# M783.net
KiCad netlist of a schematic drawn in EAGLE
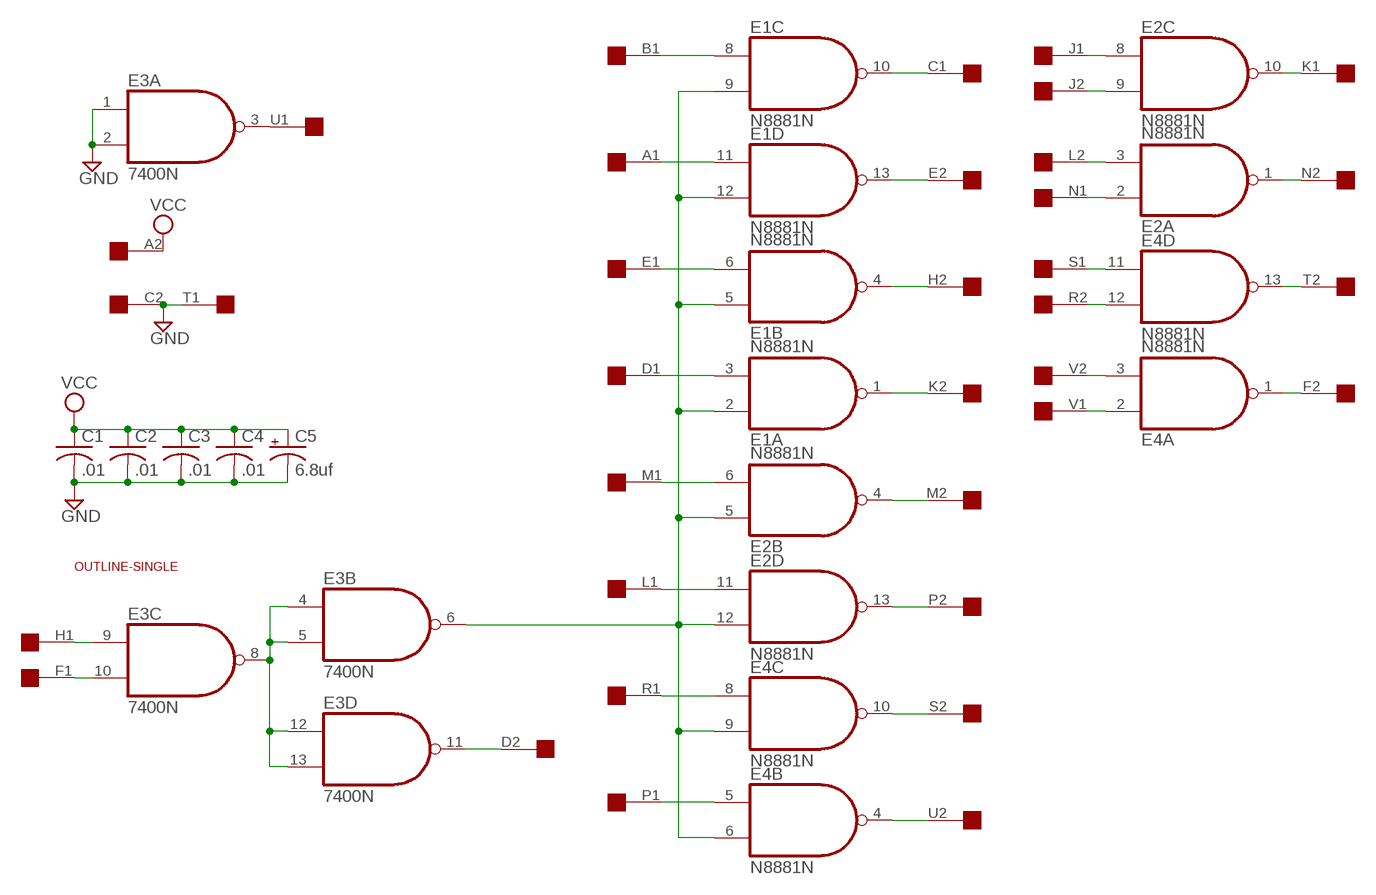
[diagram p0: schematic, sheet 1]

(export (version "E")
  (design (tool "Eeschema 10.0.6"))
  (components
    (comp (ref "C1")
      (value ".01")
      (footprint "eagle-import:C050-025X075")
      (libsource (lib "eagle-import") (part "C-US050-025X075"))
    )
    (comp (ref "C2")
      (value ".01")
      (footprint "eagle-import:C050-025X075")
      (libsource (lib "eagle-import") (part "C-US050-025X075"))
    )
    (comp (ref "C3")
      (value ".01")
      (footprint "eagle-import:C050-025X075")
      (libsource (lib "eagle-import") (part "C-US050-025X075"))
    )
    (comp (ref "C4")
      (value ".01")
      (footprint "eagle-import:C050-025X075")
      (libsource (lib "eagle-import") (part "C-US050-025X075"))
    )
    (comp (ref "C5")
      (value "6.8uf")
      (footprint "eagle-import:E15-5")
      (libsource (lib "eagle-import") (part "CPOL-USE15-5AXIAL"))
    )
    (comp (ref "E1")
      (value "N8881N")
      (footprint "eagle-import:DIL14")
      (libsource (lib "eagle-import") (part "N8881N"))
    )
    (comp (ref "E2")
      (value "N8881N")
      (footprint "eagle-import:DIL14")
      (libsource (lib "eagle-import") (part "N8881N"))
    )
    (comp (ref "E3")
      (value "7400N")
      (footprint "eagle-import:DIL14")
      (libsource (lib "eagle-import") (part "7400N"))
    )
    (comp (ref "E4")
      (value "N8881N")
      (footprint "eagle-import:DIL14")
      (libsource (lib "eagle-import") (part "N8881N"))
    )
    (comp (ref "U$1")
      (value "SINGLE")
      (footprint "eagle-import:EDGE-CON2")
      (libsource (lib "eagle-import") (part "SINGLE"))
    )
    (comp (ref "U$2")
      (value "OUTLINE-SINGLE")
      (footprint "eagle-import:SINGLE")
      (libsource (lib "eagle-import") (part "OUTLINE-SINGLE"))
    )
  )
  (nets
    (net (code "1") (name "GND") (class "Default")
      (node (ref "C1") (pin "2") (pinfunction "2_2") (pintype "passive"))
      (node (ref "C2") (pin "2") (pinfunction "2_2") (pintype "passive"))
      (node (ref "C3") (pin "2") (pinfunction "2_2") (pintype "passive"))
      (node (ref "C4") (pin "2") (pinfunction "2_2") (pintype "passive"))
      (node (ref "C5") (pin "-") (pinfunction "-_-") (pintype "passive"))
      (node (ref "E3") (pin "1") (pinfunction "I0_1") (pintype "input"))
      (node (ref "E3") (pin "2") (pinfunction "I1_2") (pintype "input"))
      (node (ref "U$1") (pin "C2") (pinfunction "1_C2") (pintype "bidirectional"))
      (node (ref "U$1") (pin "T1") (pinfunction "1_T1") (pintype "bidirectional"))
    )
    (net (code "2") (name "Net-(E1A-I0)") (class "Default")
      (node (ref "E1") (pin "12") (pinfunction "I1_12") (pintype "input"))
      (node (ref "E1") (pin "2") (pinfunction "I0_2") (pintype "input"))
      (node (ref "E1") (pin "5") (pinfunction "I0_5") (pintype "input"))
      (node (ref "E1") (pin "9") (pinfunction "I1_9") (pintype "input"))
      (node (ref "E2") (pin "12") (pinfunction "I1_12") (pintype "input"))
      (node (ref "E2") (pin "5") (pinfunction "I0_5") (pintype "input"))
      (node (ref "E3") (pin "6") (pinfunction "O_6") (pintype "output"))
      (node (ref "E4") (pin "6") (pinfunction "I1_6") (pintype "input"))
      (node (ref "E4") (pin "9") (pinfunction "I1_9") (pintype "input"))
    )
    (net (code "3") (name "Net-(E1A-I1)") (class "Default")
      (node (ref "E1") (pin "3") (pinfunction "I1_3") (pintype "input"))
      (node (ref "U$1") (pin "D1") (pinfunction "1_D1") (pintype "bidirectional"))
    )
    (net (code "4") (name "Net-(E1A-O)") (class "Default")
      (node (ref "E1") (pin "1") (pinfunction "O_1") (pintype "open_collector"))
      (node (ref "U$1") (pin "K2") (pinfunction "1_K2") (pintype "bidirectional"))
    )
    (net (code "5") (name "Net-(E1B-I1)") (class "Default")
      (node (ref "E1") (pin "6") (pinfunction "I1_6") (pintype "input"))
      (node (ref "U$1") (pin "E1") (pinfunction "1_E1") (pintype "bidirectional"))
    )
    (net (code "6") (name "Net-(E1B-O)") (class "Default")
      (node (ref "E1") (pin "4") (pinfunction "O_4") (pintype "open_collector"))
      (node (ref "U$1") (pin "H2") (pinfunction "1_H2") (pintype "bidirectional"))
    )
    (net (code "7") (name "Net-(E1C-I0)") (class "Default")
      (node (ref "E1") (pin "8") (pinfunction "I0_8") (pintype "input"))
      (node (ref "U$1") (pin "B1") (pinfunction "1_B1") (pintype "bidirectional"))
    )
    (net (code "8") (name "Net-(E1C-O)") (class "Default")
      (node (ref "E1") (pin "10") (pinfunction "O_10") (pintype "open_collector"))
      (node (ref "U$1") (pin "C1") (pinfunction "1_C1") (pintype "bidirectional"))
    )
    (net (code "9") (name "Net-(E1D-I0)") (class "Default")
      (node (ref "E1") (pin "11") (pinfunction "I0_11") (pintype "input"))
      (node (ref "U$1") (pin "A1") (pinfunction "1_A1") (pintype "bidirectional"))
    )
    (net (code "10") (name "Net-(E1D-O)") (class "Default")
      (node (ref "E1") (pin "13") (pinfunction "O_13") (pintype "open_collector"))
      (node (ref "U$1") (pin "E2") (pinfunction "1_E2") (pintype "bidirectional"))
    )
    (net (code "11") (name "Net-(E2A-I0)") (class "Default")
      (node (ref "E2") (pin "2") (pinfunction "I0_2") (pintype "input"))
      (node (ref "U$1") (pin "N1") (pinfunction "1_N1") (pintype "bidirectional"))
    )
    (net (code "12") (name "Net-(E2A-I1)") (class "Default")
      (node (ref "E2") (pin "3") (pinfunction "I1_3") (pintype "input"))
      (node (ref "U$1") (pin "L2") (pinfunction "1_L2") (pintype "bidirectional"))
    )
    (net (code "13") (name "Net-(E2A-O)") (class "Default")
      (node (ref "E2") (pin "1") (pinfunction "O_1") (pintype "open_collector"))
      (node (ref "U$1") (pin "N2") (pinfunction "1_N2") (pintype "bidirectional"))
    )
    (net (code "14") (name "Net-(E2B-I1)") (class "Default")
      (node (ref "E2") (pin "6") (pinfunction "I1_6") (pintype "input"))
      (node (ref "U$1") (pin "M1") (pinfunction "1_M1") (pintype "bidirectional"))
    )
    (net (code "15") (name "Net-(E2B-O)") (class "Default")
      (node (ref "E2") (pin "4") (pinfunction "O_4") (pintype "open_collector"))
      (node (ref "U$1") (pin "M2") (pinfunction "1_M2") (pintype "bidirectional"))
    )
    (net (code "16") (name "Net-(E2C-I0)") (class "Default")
      (node (ref "E2") (pin "8") (pinfunction "I0_8") (pintype "input"))
      (node (ref "U$1") (pin "J1") (pinfunction "1_J1") (pintype "bidirectional"))
    )
    (net (code "17") (name "Net-(E2C-I1)") (class "Default")
      (node (ref "E2") (pin "9") (pinfunction "I1_9") (pintype "input"))
      (node (ref "U$1") (pin "J2") (pinfunction "1_J2") (pintype "bidirectional"))
    )
    (net (code "18") (name "Net-(E2C-O)") (class "Default")
      (node (ref "E2") (pin "10") (pinfunction "O_10") (pintype "open_collector"))
      (node (ref "U$1") (pin "K1") (pinfunction "1_K1") (pintype "bidirectional"))
    )
    (net (code "19") (name "Net-(E2D-I0)") (class "Default")
      (node (ref "E2") (pin "11") (pinfunction "I0_11") (pintype "input"))
      (node (ref "U$1") (pin "L1") (pinfunction "1_L1") (pintype "bidirectional"))
    )
    (net (code "20") (name "Net-(E2D-O)") (class "Default")
      (node (ref "E2") (pin "13") (pinfunction "O_13") (pintype "open_collector"))
      (node (ref "U$1") (pin "P2") (pinfunction "1_P2") (pintype "bidirectional"))
    )
    (net (code "21") (name "Net-(E3A-O)") (class "Default")
      (node (ref "E3") (pin "3") (pinfunction "O_3") (pintype "output"))
      (node (ref "U$1") (pin "U1") (pinfunction "1_U1") (pintype "bidirectional"))
    )
    (net (code "22") (name "Net-(E3B-I0)") (class "Default")
      (node (ref "E3") (pin "12") (pinfunction "I0_12") (pintype "input"))
      (node (ref "E3") (pin "13") (pinfunction "I1_13") (pintype "input"))
      (node (ref "E3") (pin "4") (pinfunction "I0_4") (pintype "input"))
      (node (ref "E3") (pin "5") (pinfunction "I1_5") (pintype "input"))
      (node (ref "E3") (pin "8") (pinfunction "O_8") (pintype "output"))
    )
    (net (code "23") (name "Net-(E3C-I0)") (class "Default")
      (node (ref "E3") (pin "9") (pinfunction "I0_9") (pintype "input"))
      (node (ref "U$1") (pin "H1") (pinfunction "1_H1") (pintype "bidirectional"))
    )
    (net (code "24") (name "Net-(E3C-I1)") (class "Default")
      (node (ref "E3") (pin "10") (pinfunction "I1_10") (pintype "input"))
      (node (ref "U$1") (pin "F1") (pinfunction "1_F1") (pintype "bidirectional"))
    )
    (net (code "25") (name "Net-(E3D-O)") (class "Default")
      (node (ref "E3") (pin "11") (pinfunction "O_11") (pintype "output"))
      (node (ref "U$1") (pin "D2") (pinfunction "1_D2") (pintype "bidirectional"))
    )
    (net (code "26") (name "Net-(E4A-I0)") (class "Default")
      (node (ref "E4") (pin "2") (pinfunction "I0_2") (pintype "input"))
      (node (ref "U$1") (pin "V1") (pinfunction "1_V1") (pintype "bidirectional"))
    )
    (net (code "27") (name "Net-(E4A-I1)") (class "Default")
      (node (ref "E4") (pin "3") (pinfunction "I1_3") (pintype "input"))
      (node (ref "U$1") (pin "V2") (pinfunction "1_V2") (pintype "bidirectional"))
    )
    (net (code "28") (name "Net-(E4A-O)") (class "Default")
      (node (ref "E4") (pin "1") (pinfunction "O_1") (pintype "open_collector"))
      (node (ref "U$1") (pin "F2") (pinfunction "1_F2") (pintype "bidirectional"))
    )
    (net (code "29") (name "Net-(E4B-I0)") (class "Default")
      (node (ref "E4") (pin "5") (pinfunction "I0_5") (pintype "input"))
      (node (ref "U$1") (pin "P1") (pinfunction "1_P1") (pintype "bidirectional"))
    )
    (net (code "30") (name "Net-(E4B-O)") (class "Default")
      (node (ref "E4") (pin "4") (pinfunction "O_4") (pintype "open_collector"))
      (node (ref "U$1") (pin "U2") (pinfunction "1_U2") (pintype "bidirectional"))
    )
    (net (code "31") (name "Net-(E4C-I0)") (class "Default")
      (node (ref "E4") (pin "8") (pinfunction "I0_8") (pintype "input"))
      (node (ref "U$1") (pin "R1") (pinfunction "1_R1") (pintype "bidirectional"))
    )
    (net (code "32") (name "Net-(E4C-O)") (class "Default")
      (node (ref "E4") (pin "10") (pinfunction "O_10") (pintype "open_collector"))
      (node (ref "U$1") (pin "S2") (pinfunction "1_S2") (pintype "bidirectional"))
    )
    (net (code "33") (name "Net-(E4D-I0)") (class "Default")
      (node (ref "E4") (pin "11") (pinfunction "I0_11") (pintype "input"))
      (node (ref "U$1") (pin "S1") (pinfunction "1_S1") (pintype "bidirectional"))
    )
    (net (code "34") (name "Net-(E4D-I1)") (class "Default")
      (node (ref "E4") (pin "12") (pinfunction "I1_12") (pintype "input"))
      (node (ref "U$1") (pin "R2") (pinfunction "1_R2") (pintype "bidirectional"))
    )
    (net (code "35") (name "Net-(E4D-O)") (class "Default")
      (node (ref "E4") (pin "13") (pinfunction "O_13") (pintype "open_collector"))
      (node (ref "U$1") (pin "T2") (pinfunction "1_T2") (pintype "bidirectional"))
    )
    (net (code "36") (name "VCC") (class "Default")
      (node (ref "C1") (pin "1") (pinfunction "1_1") (pintype "passive"))
      (node (ref "C2") (pin "1") (pinfunction "1_1") (pintype "passive"))
      (node (ref "C3") (pin "1") (pinfunction "1_1") (pintype "passive"))
      (node (ref "C4") (pin "1") (pinfunction "1_1") (pintype "passive"))
      (node (ref "C5") (pin "+") (pinfunction "+_+") (pintype "passive"))
      (node (ref "U$1") (pin "A2") (pinfunction "1_A2") (pintype "bidirectional"))
    )
  )
)
